# power.net
KiCad netlist of a schematic drawn in Altium Designer
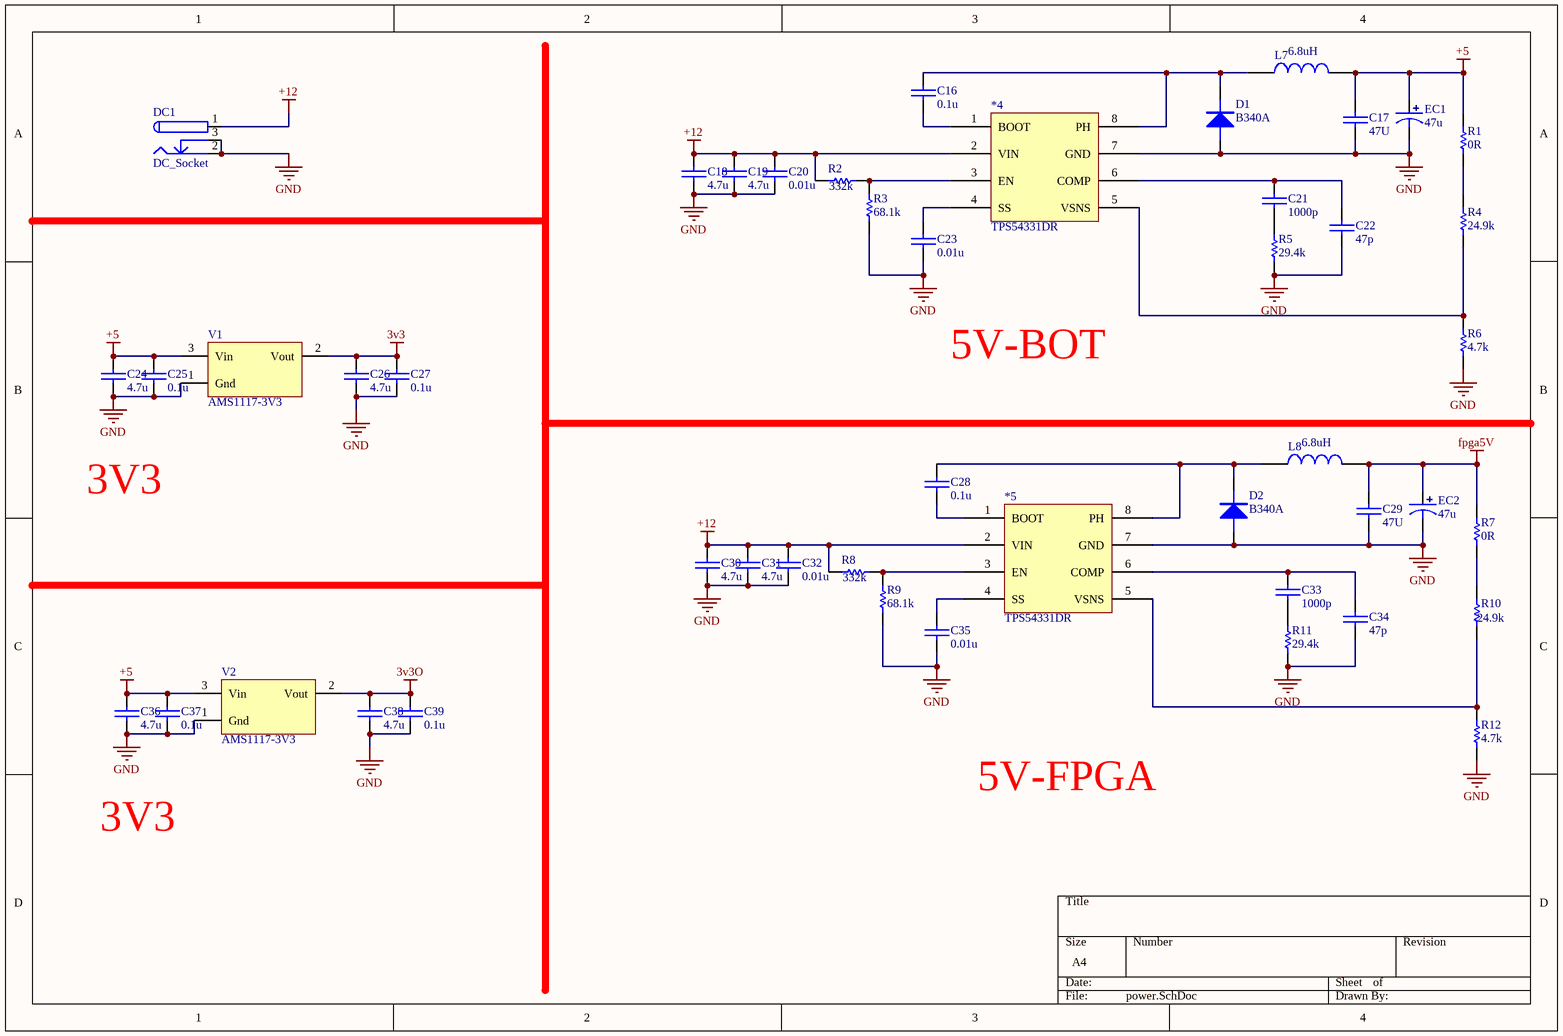
[diagram p0: power.SchDoc]

(export (version "E")
  (design (tool "Eeschema 10.0.6"))
  (components
    (comp (ref "*4")
      (value "TPS54331DR")
      (footprint "SOIC-8")
      (description "降压型DC-DC")
      (libsource (lib "0.03电源") (part "TPS54331DR"))
    )
    (comp (ref "*5")
      (value "TPS54331DR")
      (footprint "SOIC-8")
      (description "降压型DC-DC")
      (libsource (lib "0.03电源") (part "TPS54331DR"))
    )
    (comp (ref "C16")
      (value "0.1u")
      (footprint "0603C")
      (description "无极性电容")
      (libsource (lib "1.00-阻容感") (part "CAP"))
    )
    (comp (ref "C17")
      (value "47U")
      (footprint "0603C")
      (description "无极性电容")
      (libsource (lib "1.00-阻容感") (part "CAP"))
    )
    (comp (ref "C18")
      (value "4.7u")
      (footprint "0603C")
      (description "无极性电容")
      (libsource (lib "1.00-阻容感") (part "CAP"))
    )
    (comp (ref "C19")
      (value "4.7u")
      (footprint "0603C")
      (description "无极性电容")
      (libsource (lib "1.00-阻容感") (part "CAP"))
    )
    (comp (ref "C20")
      (value "0.01u")
      (footprint "0603C")
      (description "无极性电容")
      (libsource (lib "1.00-阻容感") (part "CAP"))
    )
    (comp (ref "C21")
      (value "1000p")
      (footprint "0603C")
      (description "无极性电容")
      (libsource (lib "1.00-阻容感") (part "CAP"))
    )
    (comp (ref "C22")
      (value "47p")
      (footprint "0603C")
      (description "无极性电容")
      (libsource (lib "1.00-阻容感") (part "CAP"))
    )
    (comp (ref "C23")
      (value "0.01u")
      (footprint "0603C")
      (description "无极性电容")
      (libsource (lib "1.00-阻容感") (part "CAP"))
    )
    (comp (ref "C24")
      (value "4.7u")
      (footprint "0603C")
      (description "无极性电容")
      (libsource (lib "1.00-阻容感") (part "CAP"))
    )
    (comp (ref "C25")
      (value "0.1u")
      (footprint "0603C")
      (description "无极性电容")
      (libsource (lib "1.00-阻容感") (part "CAP"))
    )
    (comp (ref "C26")
      (value "4.7u")
      (footprint "0603C")
      (description "无极性电容")
      (libsource (lib "1.00-阻容感") (part "CAP"))
    )
    (comp (ref "C27")
      (value "0.1u")
      (footprint "0603C")
      (description "无极性电容")
      (libsource (lib "1.00-阻容感") (part "CAP"))
    )
    (comp (ref "C28")
      (value "0.1u")
      (footprint "0603C")
      (description "无极性电容")
      (libsource (lib "1.00-阻容感") (part "CAP"))
    )
    (comp (ref "C29")
      (value "47U")
      (footprint "0603C")
      (description "无极性电容")
      (libsource (lib "1.00-阻容感") (part "CAP"))
    )
    (comp (ref "C30")
      (value "4.7u")
      (footprint "0603C")
      (description "无极性电容")
      (libsource (lib "1.00-阻容感") (part "CAP"))
    )
    (comp (ref "C31")
      (value "4.7u")
      (footprint "0603C")
      (description "无极性电容")
      (libsource (lib "1.00-阻容感") (part "CAP"))
    )
    (comp (ref "C32")
      (value "0.01u")
      (footprint "0603C")
      (description "无极性电容")
      (libsource (lib "1.00-阻容感") (part "CAP"))
    )
    (comp (ref "C33")
      (value "1000p")
      (footprint "0603C")
      (description "无极性电容")
      (libsource (lib "1.00-阻容感") (part "CAP"))
    )
    (comp (ref "C34")
      (value "47p")
      (footprint "0603C")
      (description "无极性电容")
      (libsource (lib "1.00-阻容感") (part "CAP"))
    )
    (comp (ref "C35")
      (value "0.01u")
      (footprint "0603C")
      (description "无极性电容")
      (libsource (lib "1.00-阻容感") (part "CAP"))
    )
    (comp (ref "C36")
      (value "4.7u")
      (footprint "0603C")
      (description "无极性电容")
      (libsource (lib "1.00-阻容感") (part "CAP"))
    )
    (comp (ref "C37")
      (value "0.1u")
      (footprint "0603C")
      (description "无极性电容")
      (libsource (lib "1.00-阻容感") (part "CAP"))
    )
    (comp (ref "C38")
      (value "4.7u")
      (footprint "0603C")
      (description "无极性电容")
      (libsource (lib "1.00-阻容感") (part "CAP"))
    )
    (comp (ref "C39")
      (value "0.1u")
      (footprint "0603C")
      (description "无极性电容")
      (libsource (lib "1.00-阻容感") (part "CAP"))
    )
    (comp (ref "D1")
      (value "B340A")
      (footprint "SMA/DO-214AC")
      (description "普通二极管")
      (libsource (lib "2.00-二极管") (part "DIODE"))
    )
    (comp (ref "D2")
      (value "B340A")
      (footprint "SMA/DO-214AC")
      (description "普通二极管")
      (libsource (lib "2.00-二极管") (part "DIODE"))
    )
    (comp (ref "DC1")
      (value "DC_Socket")
      (footprint "DC-005")
      (libsource (lib "9.05-电源插座") (part "DC_Socket"))
    )
    (comp (ref "EC1")
      (value "47u")
      (footprint "SMD-EC6.3X6.3X10")
      (description "贴片电解电容")
      (libsource (lib "1.00-阻容感") (part "ECAP"))
    )
    (comp (ref "EC2")
      (value "47u")
      (footprint "SMD-EC6.3X6.3X10")
      (description "贴片电解电容")
      (libsource (lib "1.00-阻容感") (part "ECAP"))
    )
    (comp (ref "L7")
      (value "6.8uH")
      (footprint "L-SMD-0630")
      (description "INDUCTOR")
      (libsource (lib "1.00-阻容感") (part "L"))
    )
    (comp (ref "L8")
      (value "6.8uH")
      (footprint "L-SMD-0630")
      (description "INDUCTOR")
      (libsource (lib "1.00-阻容感") (part "L"))
    )
    (comp (ref "R1")
      (value "0R")
      (footprint "0603R")
      (description "电阻")
      (libsource (lib "1.00-阻容感") (part "RES"))
    )
    (comp (ref "R2")
      (value "332k")
      (footprint "0603R")
      (description "电阻")
      (libsource (lib "1.00-阻容感") (part "RES"))
    )
    (comp (ref "R3")
      (value "68.1k")
      (footprint "0603R")
      (description "电阻")
      (libsource (lib "1.00-阻容感") (part "RES"))
    )
    (comp (ref "R4")
      (value "24.9k")
      (footprint "0603R")
      (description "电阻")
      (libsource (lib "1.00-阻容感") (part "RES"))
    )
    (comp (ref "R5")
      (value "29.4k")
      (footprint "0603R")
      (description "电阻")
      (libsource (lib "1.00-阻容感") (part "RES"))
    )
    (comp (ref "R6")
      (value "4.7k")
      (footprint "0603R")
      (description "电阻")
      (libsource (lib "1.00-阻容感") (part "RES"))
    )
    (comp (ref "R7")
      (value "0R")
      (footprint "0603R")
      (description "电阻")
      (libsource (lib "1.00-阻容感") (part "RES"))
    )
    (comp (ref "R8")
      (value "332k")
      (footprint "0603R")
      (description "电阻")
      (libsource (lib "1.00-阻容感") (part "RES"))
    )
    (comp (ref "R9")
      (value "68.1k")
      (footprint "0603R")
      (description "电阻")
      (libsource (lib "1.00-阻容感") (part "RES"))
    )
    (comp (ref "R10")
      (value "24.9k")
      (footprint "0603R")
      (description "电阻")
      (libsource (lib "1.00-阻容感") (part "RES"))
    )
    (comp (ref "R11")
      (value "29.4k")
      (footprint "0603R")
      (description "电阻")
      (libsource (lib "1.00-阻容感") (part "RES"))
    )
    (comp (ref "R12")
      (value "4.7k")
      (footprint "0603R")
      (description "电阻")
      (libsource (lib "1.00-阻容感") (part "RES"))
    )
    (comp (ref "V1")
      (value "AMS1117-3V3")
      (footprint "SOT223_L")
      (description "LDO")
      (libsource (lib "0.03电源") (part "AMS1117"))
    )
    (comp (ref "V2")
      (value "AMS1117-3V3")
      (footprint "SOT223_L")
      (description "LDO")
      (libsource (lib "0.03电源") (part "AMS1117"))
    )
  )
  (nets
    (net (code "1") (name "+5") (class "Default")
      (node (ref "C17") (pin "2") (pinfunction "2_2") (pintype "passive"))
      (node (ref "C24") (pin "2") (pinfunction "2_2") (pintype "passive"))
      (node (ref "C25") (pin "2") (pinfunction "2_2") (pintype "passive"))
      (node (ref "C36") (pin "2") (pinfunction "2_2") (pintype "passive"))
      (node (ref "C37") (pin "2") (pinfunction "2_2") (pintype "passive"))
      (node (ref "EC1") (pin "1") (pinfunction "1_1") (pintype "passive"))
      (node (ref "L7") (pin "2") (pinfunction "2_2") (pintype "passive"))
      (node (ref "R1") (pin "2") (pinfunction "2_2") (pintype "passive"))
      (node (ref "V1") (pin "3") (pinfunction "Vin_3") (pintype "passive"))
      (node (ref "V2") (pin "3") (pinfunction "Vin_3") (pintype "passive"))
    )
    (net (code "2") (name "+12") (class "Default")
      (node (ref "*4") (pin "2") (pinfunction "VIN_2") (pintype "passive"))
      (node (ref "*5") (pin "2") (pinfunction "VIN_2") (pintype "passive"))
      (node (ref "C18") (pin "2") (pinfunction "2_2") (pintype "passive"))
      (node (ref "C19") (pin "2") (pinfunction "2_2") (pintype "passive"))
      (node (ref "C20") (pin "2") (pinfunction "2_2") (pintype "passive"))
      (node (ref "C30") (pin "2") (pinfunction "2_2") (pintype "passive"))
      (node (ref "C31") (pin "2") (pinfunction "2_2") (pintype "passive"))
      (node (ref "C32") (pin "2") (pinfunction "2_2") (pintype "passive"))
      (node (ref "DC1") (pin "1") (pinfunction "1_1") (pintype "power_in"))
      (node (ref "R2") (pin "2") (pinfunction "2_2") (pintype "passive"))
      (node (ref "R8") (pin "2") (pinfunction "2_2") (pintype "passive"))
    )
    (net (code "3") (name "3v3") (class "Default")
      (node (ref "C26") (pin "2") (pinfunction "2_2") (pintype "passive"))
      (node (ref "C27") (pin "2") (pinfunction "2_2") (pintype "passive"))
      (node (ref "V1") (pin "2") (pinfunction "Vout_2") (pintype "passive"))
    )
    (net (code "4") (name "3v3O") (class "Default")
      (node (ref "C38") (pin "2") (pinfunction "2_2") (pintype "passive"))
      (node (ref "C39") (pin "2") (pinfunction "2_2") (pintype "passive"))
      (node (ref "V2") (pin "2") (pinfunction "Vout_2") (pintype "passive"))
    )
    (net (code "5") (name "GND") (class "Default")
      (node (ref "*4") (pin "7") (pinfunction "GND_7") (pintype "passive"))
      (node (ref "*5") (pin "7") (pinfunction "GND_7") (pintype "passive"))
      (node (ref "C17") (pin "1") (pinfunction "1_1") (pintype "passive"))
      (node (ref "C18") (pin "1") (pinfunction "1_1") (pintype "passive"))
      (node (ref "C19") (pin "1") (pinfunction "1_1") (pintype "passive"))
      (node (ref "C20") (pin "1") (pinfunction "1_1") (pintype "passive"))
      (node (ref "C22") (pin "1") (pinfunction "1_1") (pintype "passive"))
      (node (ref "C23") (pin "1") (pinfunction "1_1") (pintype "passive"))
      (node (ref "C24") (pin "1") (pinfunction "1_1") (pintype "passive"))
      (node (ref "C25") (pin "1") (pinfunction "1_1") (pintype "passive"))
      (node (ref "C26") (pin "1") (pinfunction "1_1") (pintype "passive"))
      (node (ref "C27") (pin "1") (pinfunction "1_1") (pintype "passive"))
      (node (ref "C29") (pin "1") (pinfunction "1_1") (pintype "passive"))
      (node (ref "C30") (pin "1") (pinfunction "1_1") (pintype "passive"))
      (node (ref "C31") (pin "1") (pinfunction "1_1") (pintype "passive"))
      (node (ref "C32") (pin "1") (pinfunction "1_1") (pintype "passive"))
      (node (ref "C34") (pin "1") (pinfunction "1_1") (pintype "passive"))
      (node (ref "C35") (pin "1") (pinfunction "1_1") (pintype "passive"))
      (node (ref "C36") (pin "1") (pinfunction "1_1") (pintype "passive"))
      (node (ref "C37") (pin "1") (pinfunction "1_1") (pintype "passive"))
      (node (ref "C38") (pin "1") (pinfunction "1_1") (pintype "passive"))
      (node (ref "C39") (pin "1") (pinfunction "1_1") (pintype "passive"))
      (node (ref "D1") (pin "A") (pinfunction "A_A") (pintype "passive"))
      (node (ref "D2") (pin "A") (pinfunction "A_A") (pintype "passive"))
      (node (ref "DC1") (pin "2") (pinfunction "2_2") (pintype "power_in"))
      (node (ref "DC1") (pin "3") (pinfunction "3_3") (pintype "power_in"))
      (node (ref "EC1") (pin "2") (pinfunction "2_2") (pintype "passive"))
      (node (ref "EC2") (pin "2") (pinfunction "2_2") (pintype "passive"))
      (node (ref "R11") (pin "1") (pinfunction "1_1") (pintype "passive"))
      (node (ref "R12") (pin "1") (pinfunction "1_1") (pintype "passive"))
      (node (ref "R3") (pin "1") (pinfunction "1_1") (pintype "passive"))
      (node (ref "R5") (pin "1") (pinfunction "1_1") (pintype "passive"))
      (node (ref "R6") (pin "1") (pinfunction "1_1") (pintype "passive"))
      (node (ref "R9") (pin "1") (pinfunction "1_1") (pintype "passive"))
      (node (ref "V1") (pin "1") (pinfunction "Gnd_1") (pintype "passive"))
      (node (ref "V2") (pin "1") (pinfunction "Gnd_1") (pintype "passive"))
    )
    (net (code "6") (name "Net-(*4-BOOT)") (class "Default")
      (node (ref "*4") (pin "1") (pinfunction "BOOT_1") (pintype "passive"))
      (node (ref "C16") (pin "1") (pinfunction "1_1") (pintype "passive"))
    )
    (net (code "7") (name "Net-(*4-COMP)") (class "Default")
      (node (ref "*4") (pin "6") (pinfunction "COMP_6") (pintype "passive"))
      (node (ref "C21") (pin "2") (pinfunction "2_2") (pintype "passive"))
      (node (ref "C22") (pin "2") (pinfunction "2_2") (pintype "passive"))
    )
    (net (code "8") (name "Net-(*4-EN)") (class "Default")
      (node (ref "*4") (pin "3") (pinfunction "EN_3") (pintype "passive"))
      (node (ref "R2") (pin "1") (pinfunction "1_1") (pintype "passive"))
      (node (ref "R3") (pin "2") (pinfunction "2_2") (pintype "passive"))
    )
    (net (code "9") (name "Net-(*4-PH)") (class "Default")
      (node (ref "*4") (pin "8") (pinfunction "PH_8") (pintype "passive"))
      (node (ref "C16") (pin "2") (pinfunction "2_2") (pintype "passive"))
      (node (ref "D1") (pin "K") (pinfunction "K_K") (pintype "passive"))
      (node (ref "L7") (pin "1") (pinfunction "1_1") (pintype "passive"))
    )
    (net (code "10") (name "Net-(*4-SS)") (class "Default")
      (node (ref "*4") (pin "4") (pinfunction "SS_4") (pintype "passive"))
      (node (ref "C23") (pin "2") (pinfunction "2_2") (pintype "passive"))
    )
    (net (code "11") (name "Net-(*4-VSNS)") (class "Default")
      (node (ref "*4") (pin "5") (pinfunction "VSNS_5") (pintype "passive"))
      (node (ref "R4") (pin "1") (pinfunction "1_1") (pintype "passive"))
      (node (ref "R6") (pin "2") (pinfunction "2_2") (pintype "passive"))
    )
    (net (code "12") (name "Net-(*5-BOOT)") (class "Default")
      (node (ref "*5") (pin "1") (pinfunction "BOOT_1") (pintype "passive"))
      (node (ref "C28") (pin "1") (pinfunction "1_1") (pintype "passive"))
    )
    (net (code "13") (name "Net-(*5-COMP)") (class "Default")
      (node (ref "*5") (pin "6") (pinfunction "COMP_6") (pintype "passive"))
      (node (ref "C33") (pin "2") (pinfunction "2_2") (pintype "passive"))
      (node (ref "C34") (pin "2") (pinfunction "2_2") (pintype "passive"))
    )
    (net (code "14") (name "Net-(*5-EN)") (class "Default")
      (node (ref "*5") (pin "3") (pinfunction "EN_3") (pintype "passive"))
      (node (ref "R8") (pin "1") (pinfunction "1_1") (pintype "passive"))
      (node (ref "R9") (pin "2") (pinfunction "2_2") (pintype "passive"))
    )
    (net (code "15") (name "Net-(*5-PH)") (class "Default")
      (node (ref "*5") (pin "8") (pinfunction "PH_8") (pintype "passive"))
      (node (ref "C28") (pin "2") (pinfunction "2_2") (pintype "passive"))
      (node (ref "D2") (pin "K") (pinfunction "K_K") (pintype "passive"))
      (node (ref "L8") (pin "1") (pinfunction "1_1") (pintype "passive"))
    )
    (net (code "16") (name "Net-(*5-SS)") (class "Default")
      (node (ref "*5") (pin "4") (pinfunction "SS_4") (pintype "passive"))
      (node (ref "C35") (pin "2") (pinfunction "2_2") (pintype "passive"))
    )
    (net (code "17") (name "Net-(*5-VSNS)") (class "Default")
      (node (ref "*5") (pin "5") (pinfunction "VSNS_5") (pintype "passive"))
      (node (ref "R10") (pin "1") (pinfunction "1_1") (pintype "passive"))
      (node (ref "R12") (pin "2") (pinfunction "2_2") (pintype "passive"))
    )
    (net (code "18") (name "Net-(C21-Pad1)") (class "Default")
      (node (ref "C21") (pin "1") (pinfunction "1_1") (pintype "passive"))
      (node (ref "R5") (pin "2") (pinfunction "2_2") (pintype "passive"))
    )
    (net (code "19") (name "Net-(C33-Pad1)") (class "Default")
      (node (ref "C33") (pin "1") (pinfunction "1_1") (pintype "passive"))
      (node (ref "R11") (pin "2") (pinfunction "2_2") (pintype "passive"))
    )
    (net (code "20") (name "Net-(R1-Pad1)") (class "Default")
      (node (ref "R1") (pin "1") (pinfunction "1_1") (pintype "passive"))
      (node (ref "R4") (pin "2") (pinfunction "2_2") (pintype "passive"))
    )
    (net (code "21") (name "Net-(R10-Pad2)") (class "Default")
      (node (ref "R10") (pin "2") (pinfunction "2_2") (pintype "passive"))
      (node (ref "R7") (pin "1") (pinfunction "1_1") (pintype "passive"))
    )
    (net (code "22") (name "fpga5V") (class "Default")
      (node (ref "C29") (pin "2") (pinfunction "2_2") (pintype "passive"))
      (node (ref "EC2") (pin "1") (pinfunction "1_1") (pintype "passive"))
      (node (ref "L8") (pin "2") (pinfunction "2_2") (pintype "passive"))
      (node (ref "R7") (pin "2") (pinfunction "2_2") (pintype "passive"))
    )
  )
)
